# Sheet1.net
KiCad netlist of a schematic drawn in Altium Designer
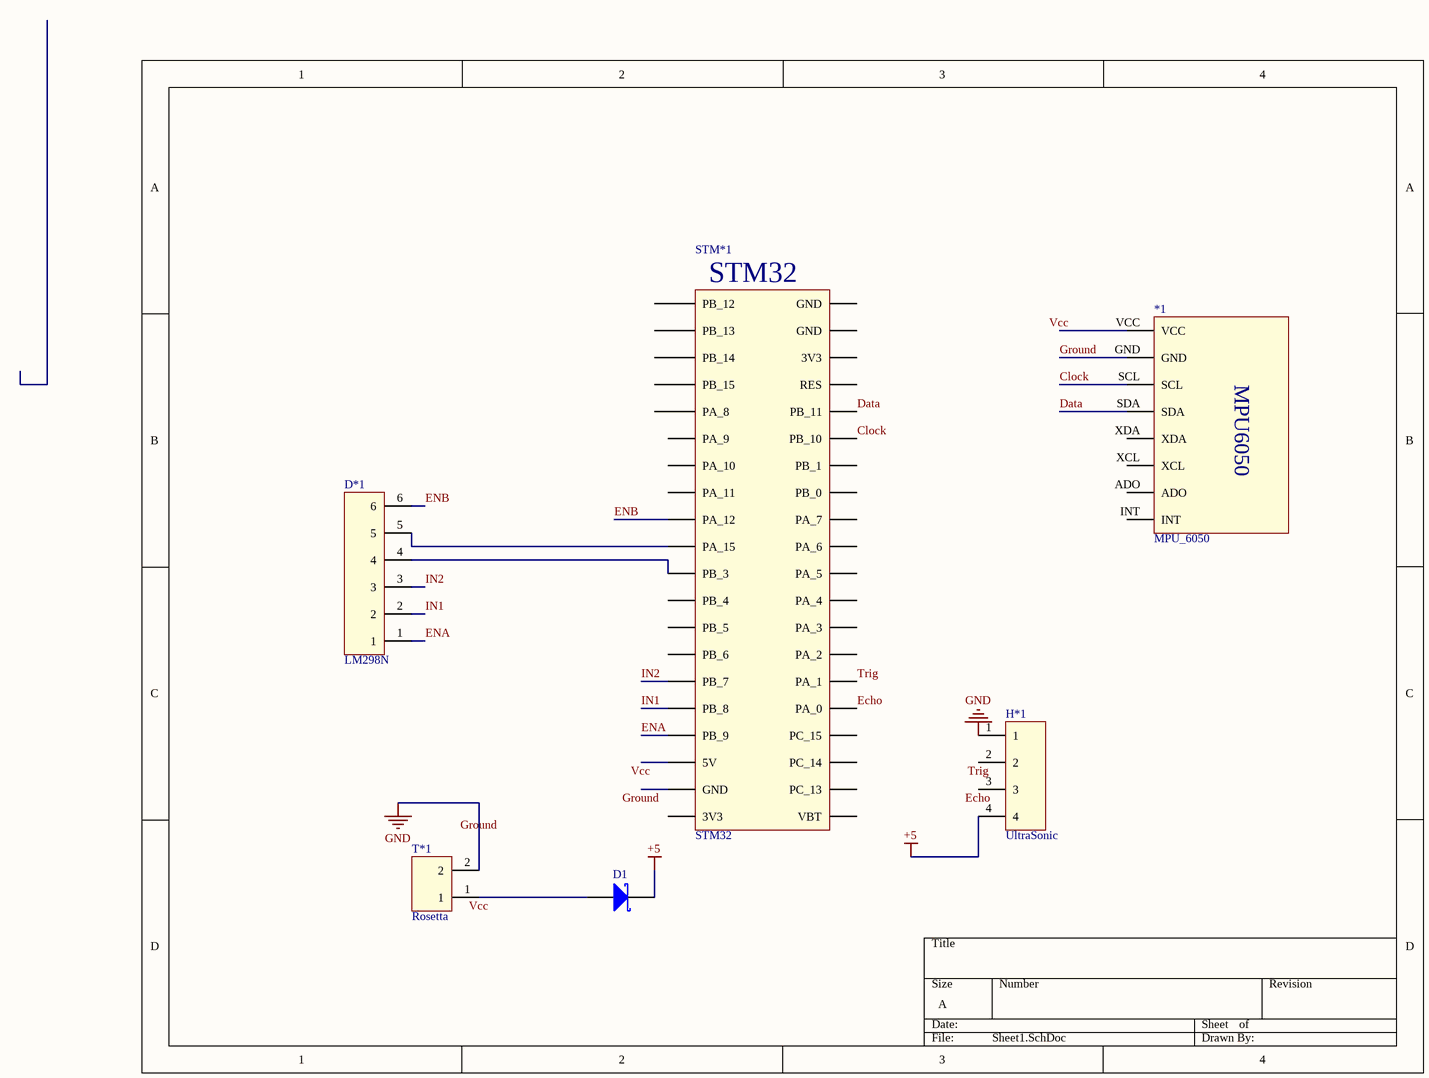
[diagram p0: Sheet1.SchDoc]

(export (version "E")
  (design (tool "Eeschema 10.0.6"))
  (components
    (comp (ref "*1")
      (value "MPU_6050")
      (footprint "MPU6050")
      (libsource (lib "Mia_Training") (part "MPU_6050"))
    )
    (comp (ref "D*1")
      (value "LM298N")
      (footprint "DATA_PIN_HEADER_6_2.54m")
      (libsource (lib "Mia_Training") (part "DATA_PIN_HEADER_6_2.54m"))
    )
    (comp (ref "D1")
      (value "Schottky Diode")
      (libsource (lib "Simulation Generic Components") (part "Schottky Diode"))
    )
    (comp (ref "H*1")
      (value "UltraSonic")
      (footprint "Female_Header_4")
      (libsource (lib "Mia_Training") (part "FEMALE_HEADER_4"))
    )
    (comp (ref "STM*1") (value "STM32") (footprint "STM32") (libsource (lib "Mia_Training") (part "STM32")))
    (comp (ref "T*1")
      (value "Rosetta")
      (footprint "Terminal_block_2pins_3.5mm")
      (libsource (lib "Mia_Training") (part "Terminal_block_2pins_3.5mm"))
    )
  )
  (nets
    (net (code "1") (name "+5") (class "Default")
      (node (ref "D1") (pin "2") (pinfunction "K_2") (pintype "passive"))
      (node (ref "H*1") (pin "4") (pinfunction "4_4") (pintype "passive"))
    )
    (net (code "2") (name "/Clock") (class "Default")
      (node (ref "*1") (pin "SCL") (pinfunction "SCL_SCL") (pintype "passive"))
      (node (ref "STM*1") (pin "PB_10") (pinfunction "PB_10_PB_10") (pintype "passive"))
    )
    (net (code "3") (name "/Data") (class "Default")
      (node (ref "*1") (pin "SDA") (pinfunction "SDA_SDA") (pintype "passive"))
      (node (ref "STM*1") (pin "PB_11") (pinfunction "PB_11_PB_11") (pintype "passive"))
    )
    (net (code "4") (name "/ENA") (class "Default")
      (node (ref "D*1") (pin "1") (pinfunction "1_1") (pintype "passive"))
      (node (ref "STM*1") (pin "PB_9") (pinfunction "PB_9_PB_9") (pintype "passive"))
    )
    (net (code "5") (name "/ENB") (class "Default")
      (node (ref "D*1") (pin "6") (pinfunction "6_6") (pintype "passive"))
      (node (ref "STM*1") (pin "PA_12") (pinfunction "PA_12_PA_12") (pintype "passive"))
    )
    (net (code "6") (name "/Echo") (class "Default")
      (node (ref "H*1") (pin "3") (pinfunction "3_3") (pintype "passive"))
      (node (ref "STM*1") (pin "PA_0") (pinfunction "PA_0_PA_0") (pintype "passive"))
    )
    (net (code "7") (name "/IN1") (class "Default")
      (node (ref "D*1") (pin "2") (pinfunction "2_2") (pintype "passive"))
      (node (ref "STM*1") (pin "PB_8") (pinfunction "PB_8_PB_8") (pintype "passive"))
    )
    (net (code "8") (name "/IN2") (class "Default")
      (node (ref "D*1") (pin "3") (pinfunction "3_3") (pintype "passive"))
      (node (ref "STM*1") (pin "PB_7") (pinfunction "PB_7_PB_7") (pintype "passive"))
    )
    (net (code "9") (name "/Trig") (class "Default")
      (node (ref "H*1") (pin "2") (pinfunction "2_2") (pintype "passive"))
      (node (ref "STM*1") (pin "PA_1") (pinfunction "PA_1_PA_1") (pintype "passive"))
    )
    (net (code "10") (name "/Vcc") (class "Default")
      (node (ref "*1") (pin "VCC") (pinfunction "VCC_VCC") (pintype "passive"))
      (node (ref "D1") (pin "1") (pinfunction "A_1") (pintype "passive"))
      (node (ref "STM*1") (pin "5V") (pinfunction "5V_5V") (pintype "passive"))
      (node (ref "T*1") (pin "1") (pinfunction "1_1") (pintype "passive"))
    )
    (net (code "11") (name "GND") (class "Default")
      (node (ref "*1") (pin "GND") (pinfunction "GND_GND") (pintype "passive"))
      (node (ref "H*1") (pin "1") (pinfunction "1_1") (pintype "passive"))
      (node (ref "STM*1") (pin "GND") (pinfunction "GND_GND") (pintype "passive"))
      (node (ref "T*1") (pin "2") (pinfunction "2_2") (pintype "passive"))
    )
    (net (code "12") (name "Net-(D*1-Pad4)") (class "Default")
      (node (ref "D*1") (pin "4") (pinfunction "4_4") (pintype "passive"))
      (node (ref "STM*1") (pin "PB_3") (pinfunction "PB_3_PB_3") (pintype "passive"))
    )
    (net (code "13") (name "Net-(D*1-Pad5)") (class "Default")
      (node (ref "D*1") (pin "5") (pinfunction "5_5") (pintype "passive"))
      (node (ref "STM*1") (pin "PA_15") (pinfunction "PA_15_PA_15") (pintype "passive"))
    )
    (net (code "14") (name "unconnected-(*1-PadADO)") (class "Default")
      (node (ref "*1") (pin "ADO") (pinfunction "ADO_ADO") (pintype "passive"))
    )
    (net (code "15") (name "unconnected-(*1-PadINT)") (class "Default")
      (node (ref "*1") (pin "INT") (pinfunction "INT_INT") (pintype "passive"))
    )
    (net (code "16") (name "unconnected-(*1-PadXCL)") (class "Default")
      (node (ref "*1") (pin "XCL") (pinfunction "XCL_XCL") (pintype "passive"))
    )
    (net (code "17") (name "unconnected-(*1-PadXDA)") (class "Default")
      (node (ref "*1") (pin "XDA") (pinfunction "XDA_XDA") (pintype "passive"))
    )
    (net (code "18") (name "unconnected-(STM*1-Pad3V3)") (class "Default")
      (node (ref "STM*1") (pin "3V3") (pinfunction "3V3_3V3") (pintype "passive"))
    )
    (net (code "19") (name "unconnected-(STM*1-Pad3V3)_1") (class "Default")
      (node (ref "STM*1") (pin "3V3") (pinfunction "3V3_3V3") (pintype "passive"))
    )
    (net (code "20") (name "unconnected-(STM*1-PadGND)") (class "Default")
      (node (ref "STM*1") (pin "GND") (pinfunction "GND_GND") (pintype "passive"))
    )
    (net (code "21") (name "unconnected-(STM*1-PadGND)_1") (class "Default")
      (node (ref "STM*1") (pin "GND") (pinfunction "GND_GND") (pintype "passive"))
    )
    (net (code "22") (name "unconnected-(STM*1-PadPA_2)") (class "Default")
      (node (ref "STM*1") (pin "PA_2") (pinfunction "PA_2_PA_2") (pintype "passive"))
    )
    (net (code "23") (name "unconnected-(STM*1-PadPA_3)") (class "Default")
      (node (ref "STM*1") (pin "PA_3") (pinfunction "PA_3_PA_3") (pintype "passive"))
    )
    (net (code "24") (name "unconnected-(STM*1-PadPA_4)") (class "Default")
      (node (ref "STM*1") (pin "PA_4") (pinfunction "PA_4_PA_4") (pintype "passive"))
    )
    (net (code "25") (name "unconnected-(STM*1-PadPA_5)") (class "Default")
      (node (ref "STM*1") (pin "PA_5") (pinfunction "PA_5_PA_5") (pintype "passive"))
    )
    (net (code "26") (name "unconnected-(STM*1-PadPA_6)") (class "Default")
      (node (ref "STM*1") (pin "PA_6") (pinfunction "PA_6_PA_6") (pintype "passive"))
    )
    (net (code "27") (name "unconnected-(STM*1-PadPA_7)") (class "Default")
      (node (ref "STM*1") (pin "PA_7") (pinfunction "PA_7_PA_7") (pintype "passive"))
    )
    (net (code "28") (name "unconnected-(STM*1-PadPA_8)") (class "Default")
      (node (ref "STM*1") (pin "PA_8") (pinfunction "PA_8_PA_8") (pintype "passive"))
    )
    (net (code "29") (name "unconnected-(STM*1-PadPA_9)") (class "Default")
      (node (ref "STM*1") (pin "PA_9") (pinfunction "PA_9_PA_9") (pintype "passive"))
    )
    (net (code "30") (name "unconnected-(STM*1-PadPA_10)") (class "Default")
      (node (ref "STM*1") (pin "PA_10") (pinfunction "PA_10_PA_10") (pintype "passive"))
    )
    (net (code "31") (name "unconnected-(STM*1-PadPA_11)") (class "Default")
      (node (ref "STM*1") (pin "PA_11") (pinfunction "PA_11_PA_11") (pintype "passive"))
    )
    (net (code "32") (name "unconnected-(STM*1-PadPB_0)") (class "Default")
      (node (ref "STM*1") (pin "PB_0") (pinfunction "PB_0_PB_0") (pintype "passive"))
    )
    (net (code "33") (name "unconnected-(STM*1-PadPB_1)") (class "Default")
      (node (ref "STM*1") (pin "PB_1") (pinfunction "PB_1_PB_1") (pintype "passive"))
    )
    (net (code "34") (name "unconnected-(STM*1-PadPB_4)") (class "Default")
      (node (ref "STM*1") (pin "PB_4") (pinfunction "PB_4_PB_4") (pintype "passive"))
    )
    (net (code "35") (name "unconnected-(STM*1-PadPB_5)") (class "Default")
      (node (ref "STM*1") (pin "PB_5") (pinfunction "PB_5_PB_5") (pintype "passive"))
    )
    (net (code "36") (name "unconnected-(STM*1-PadPB_6)") (class "Default")
      (node (ref "STM*1") (pin "PB_6") (pinfunction "PB_6_PB_6") (pintype "passive"))
    )
    (net (code "37") (name "unconnected-(STM*1-PadPB_12)") (class "Default")
      (node (ref "STM*1") (pin "PB_12") (pinfunction "PB_12_PB_12") (pintype "passive"))
    )
    (net (code "38") (name "unconnected-(STM*1-PadPB_13)") (class "Default")
      (node (ref "STM*1") (pin "PB_13") (pinfunction "PB_13_PB_13") (pintype "passive"))
    )
    (net (code "39") (name "unconnected-(STM*1-PadPB_14)") (class "Default")
      (node (ref "STM*1") (pin "PB_14") (pinfunction "PB_14_PB_14") (pintype "passive"))
    )
    (net (code "40") (name "unconnected-(STM*1-PadPB_15)") (class "Default")
      (node (ref "STM*1") (pin "PB_15") (pinfunction "PB_15_PB_15") (pintype "passive"))
    )
    (net (code "41") (name "unconnected-(STM*1-PadPC_13)") (class "Default")
      (node (ref "STM*1") (pin "PC_13") (pinfunction "PC_13_PC_13") (pintype "passive"))
    )
    (net (code "42") (name "unconnected-(STM*1-PadPC_14)") (class "Default")
      (node (ref "STM*1") (pin "PC_14") (pinfunction "PC_14_PC_14") (pintype "passive"))
    )
    (net (code "43") (name "unconnected-(STM*1-PadPC_15)") (class "Default")
      (node (ref "STM*1") (pin "PC_15") (pinfunction "PC_15_PC_15") (pintype "passive"))
    )
    (net (code "44") (name "unconnected-(STM*1-PadRES)") (class "Default")
      (node (ref "STM*1") (pin "RES") (pinfunction "RES_RES") (pintype "passive"))
    )
    (net (code "45") (name "unconnected-(STM*1-PadVBT)") (class "Default")
      (node (ref "STM*1") (pin "VBT") (pinfunction "VBT_VBT") (pintype "passive"))
    )
  )
)
